# WifiTracker.net
KiCad netlist of a schematic drawn in EAGLE
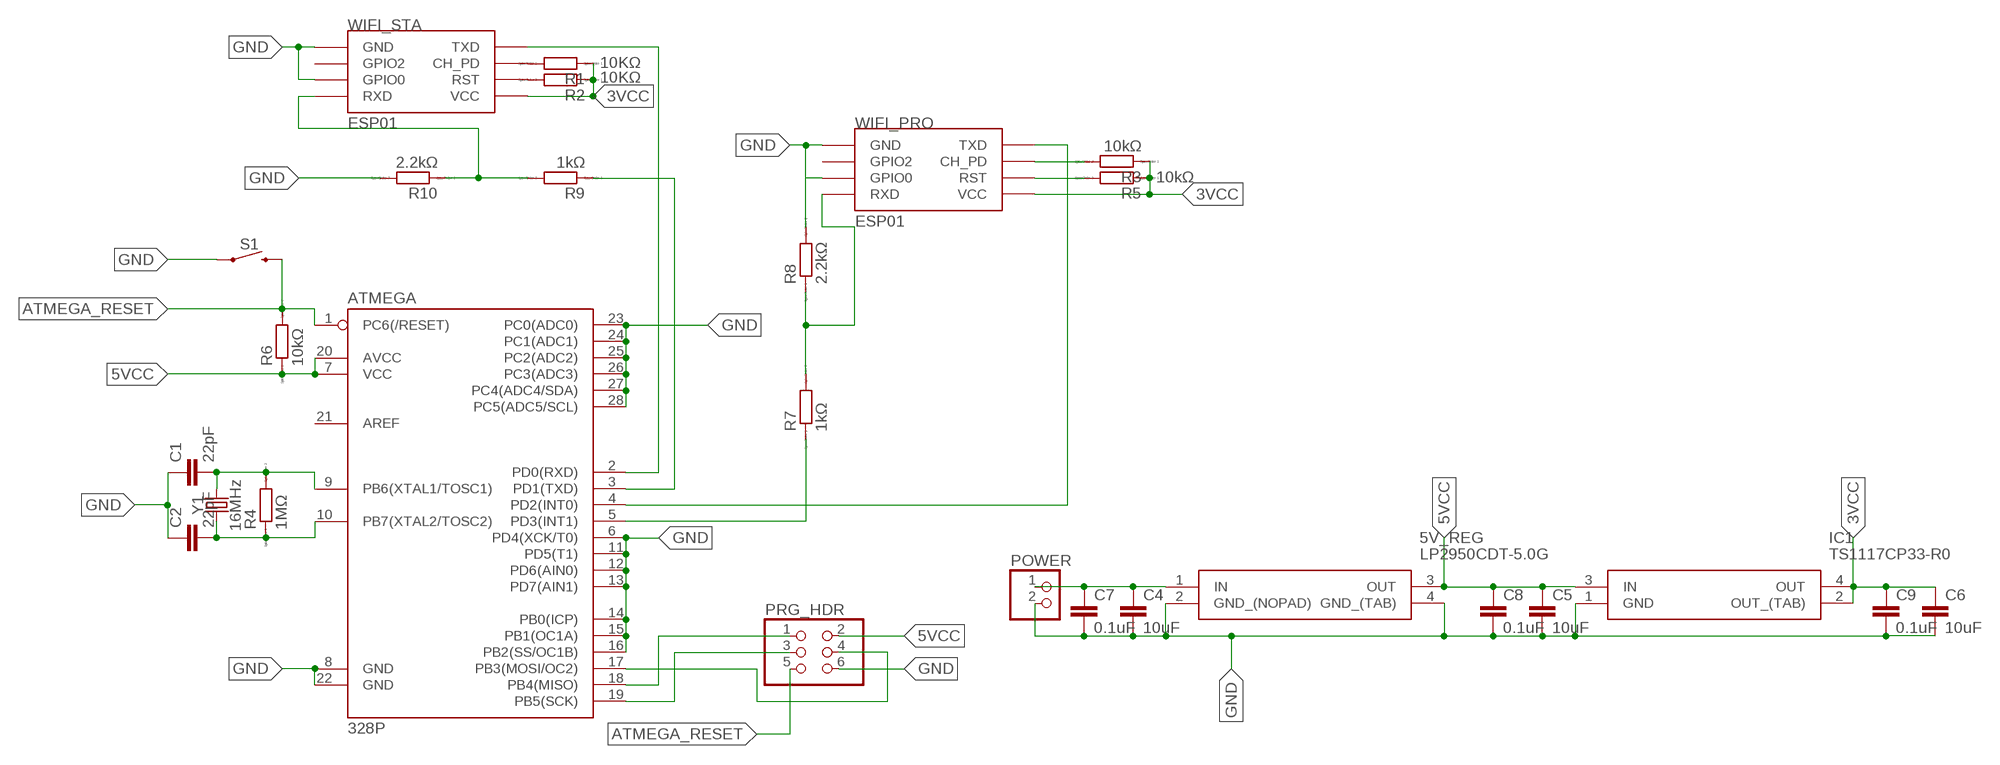
[diagram p0: schematic, sheet 1]

(export (version "E")
  (design (tool "Eeschema 10.0.6"))
  (components
    (comp (ref "5V_REG")
      (value "LP2950CDT-5.0G")
      (footprint "eagle-import:TO229P990X238-4N")
      (fields
        (field (name "MOUSER_PART_NUMBER") "863-LP2950CDT-5.0G")
        (field (name "RS_PART_NUMBER") "0463593P")
      )
      (libsource (lib "eagle-import") (part "LP2950CDT-5.0G"))
    )
    (comp (ref "ATMEGA")
      (value "328P")
      (footprint "eagle-import:DIP28")
      (libsource (lib "eagle-import") (part "ATMEGA328P_PDIP"))
    )
    (comp (ref "C1")
      (value "22pF")
      (footprint "eagle-import:1206")
      (libsource (lib "eagle-import") (part "1.0UF-1206-50V-10%"))
    )
    (comp (ref "C2")
      (value "22pF")
      (footprint "eagle-import:1206")
      (libsource (lib "eagle-import") (part "1.0UF-1206-50V-10%"))
    )
    (comp (ref "C4")
      (value "10uF")
      (footprint "eagle-import:1206")
      (libsource (lib "eagle-import") (part "1.0UF-1206-50V-10%"))
    )
    (comp (ref "C5")
      (value "10uF")
      (footprint "eagle-import:1206")
      (libsource (lib "eagle-import") (part "1.0UF-1206-50V-10%"))
    )
    (comp (ref "C6")
      (value "10uF")
      (footprint "eagle-import:1206")
      (libsource (lib "eagle-import") (part "1.0UF-1206-50V-10%"))
    )
    (comp (ref "C7")
      (value "0.1uF")
      (footprint "eagle-import:1206")
      (libsource (lib "eagle-import") (part "1.0UF-1206-50V-10%"))
    )
    (comp (ref "C8")
      (value "0.1uF")
      (footprint "eagle-import:1206")
      (libsource (lib "eagle-import") (part "1.0UF-1206-50V-10%"))
    )
    (comp (ref "C9")
      (value "0.1uF")
      (footprint "eagle-import:1206")
      (libsource (lib "eagle-import") (part "1.0UF-1206-50V-10%"))
    )
    (comp (ref "IC1")
      (value "TS1117CP33-R0")
      (footprint "eagle-import:TO229P990X238-4N")
      (fields
        (field (name "MANUFACTURER_PART_NUMBER") "LP2950CDT-5.0G")
        (field (name "MOUSER_PART_NUMBER") "863-LP2950CDT-5.0G")
        (field (name "RS_PART_NUMBER") "0463593P")
      )
      (libsource (lib "eagle-import") (part "TS1117CP33-R0"))
    )
    (comp (ref "POWER")
      (value "PINHD-1X2")
      (footprint "eagle-import:1X02")
      (libsource (lib "eagle-import") (part "PINHD-1X2"))
    )
    (comp (ref "PRG_HDR")
      (value "PINHD-2X3")
      (footprint "eagle-import:2X03")
      (libsource (lib "eagle-import") (part "PINHD-2X3"))
    )
    (comp (ref "R1")
      (value "10KΩ")
      (footprint "eagle-import:R1210")
      (libsource (lib "eagle-import") (part "RR1210"))
    )
    (comp (ref "R2")
      (value "10KΩ")
      (footprint "eagle-import:R1210")
      (libsource (lib "eagle-import") (part "RR1210"))
    )
    (comp (ref "R3")
      (value "10kΩ")
      (footprint "eagle-import:R1210")
      (libsource (lib "eagle-import") (part "RR1210"))
    )
    (comp (ref "R4")
      (value "1MΩ")
      (footprint "eagle-import:R1210")
      (libsource (lib "eagle-import") (part "RR1210"))
    )
    (comp (ref "R5")
      (value "10kΩ")
      (footprint "eagle-import:R1210")
      (libsource (lib "eagle-import") (part "RR1210"))
    )
    (comp (ref "R6")
      (value "10kΩ")
      (footprint "eagle-import:R1210")
      (libsource (lib "eagle-import") (part "RR1210"))
    )
    (comp (ref "R7")
      (value "1kΩ")
      (footprint "eagle-import:R1210")
      (libsource (lib "eagle-import") (part "RR1210"))
    )
    (comp (ref "R8")
      (value "2.2kΩ")
      (footprint "eagle-import:R1210")
      (libsource (lib "eagle-import") (part "RR1210"))
    )
    (comp (ref "R9")
      (value "1kΩ")
      (footprint "eagle-import:R1210")
      (libsource (lib "eagle-import") (part "RR1210"))
    )
    (comp (ref "R10")
      (value "2.2kΩ")
      (footprint "eagle-import:R1210")
      (libsource (lib "eagle-import") (part "RR1210"))
    )
    (comp (ref "S1")
      (value "MOMENTARY-SWITCH-SPST-PTH-6.0MM")
      (footprint "eagle-import:TACTILE_SWITCH_PTH_6.0MM")
      (libsource (lib "eagle-import") (part "MOMENTARY-SWITCH-SPST-PTH-6.0MM"))
    )
    (comp (ref "WIFI_PRO")
      (value "ESP01")
      (footprint "eagle-import:ESP01")
      (libsource (lib "eagle-import") (part "ESP01"))
    )
    (comp (ref "WIFI_STA")
      (value "ESP01")
      (footprint "eagle-import:ESP01")
      (libsource (lib "eagle-import") (part "ESP01"))
    )
    (comp (ref "Y1")
      (value "16MHz")
      (footprint "eagle-import:HC49UP")
      (libsource (lib "eagle-import") (part "CRYSTAL-8MHZSMD-HC49UP"))
    )
  )
  (nets
    (net (code "1") (name "3VCC") (class "Default")
      (node (ref "C6") (pin "1") (pinfunction "1_1") (pintype "passive"))
      (node (ref "C9") (pin "1") (pinfunction "1_1") (pintype "passive"))
      (node (ref "IC1") (pin "2") (pinfunction "OUT_(TAB)_2") (pintype "output"))
      (node (ref "IC1") (pin "4") (pinfunction "OUT_4") (pintype "output"))
      (node (ref "R1") (pin "1") (pinfunction "1_1") (pintype "passive"))
      (node (ref "R2") (pin "1") (pinfunction "1_1") (pintype "passive"))
      (node (ref "R3") (pin "1") (pinfunction "1_1") (pintype "passive"))
      (node (ref "R5") (pin "1") (pinfunction "1_1") (pintype "passive"))
      (node (ref "WIFI_PRO") (pin "VCC") (pinfunction "VCC_VCC") (pintype "bidirectional"))
      (node (ref "WIFI_STA") (pin "VCC") (pinfunction "VCC_VCC") (pintype "bidirectional"))
    )
    (net (code "2") (name "5VCC") (class "Default")
      (node (ref "5V_REG") (pin "3") (pinfunction "OUT_3") (pintype "output"))
      (node (ref "ATMEGA") (pin "20") (pinfunction "AVCC_20") (pintype "bidirectional"))
      (node (ref "ATMEGA") (pin "7") (pinfunction "VCC_7") (pintype "bidirectional"))
      (node (ref "C5") (pin "1") (pinfunction "1_1") (pintype "passive"))
      (node (ref "C8") (pin "1") (pinfunction "1_1") (pintype "passive"))
      (node (ref "IC1") (pin "3") (pinfunction "IN_3") (pintype "input"))
      (node (ref "PRG_HDR") (pin "2") (pinfunction "2_2") (pintype "passive"))
      (node (ref "R6") (pin "1") (pinfunction "1_1") (pintype "passive"))
    )
    (net (code "3") (name "ATMEGA_RESET") (class "Default")
      (node (ref "ATMEGA") (pin "1") (pinfunction "PC6(/RESET)_1") (pintype "bidirectional"))
      (node (ref "PRG_HDR") (pin "5") (pinfunction "5_5") (pintype "passive"))
      (node (ref "R6") (pin "2") (pinfunction "2_2") (pintype "passive"))
      (node (ref "S1") (pin "3") (pinfunction "2_3") (pintype "passive"))
    )
    (net (code "4") (name "GND") (class "Default")
      (node (ref "5V_REG") (pin "2") (pinfunction "GND_(NOPAD)_2") (pintype "power_in"))
      (node (ref "5V_REG") (pin "4") (pinfunction "GND_(TAB)_4") (pintype "power_in"))
      (node (ref "ATMEGA") (pin "11") (pinfunction "PD5(T1)_11") (pintype "bidirectional"))
      (node (ref "ATMEGA") (pin "12") (pinfunction "PD6(AIN0)_12") (pintype "bidirectional"))
      (node (ref "ATMEGA") (pin "13") (pinfunction "PD7(AIN1)_13") (pintype "bidirectional"))
      (node (ref "ATMEGA") (pin "14") (pinfunction "PB0(ICP)_14") (pintype "bidirectional"))
      (node (ref "ATMEGA") (pin "15") (pinfunction "PB1(OC1A)_15") (pintype "bidirectional"))
      (node (ref "ATMEGA") (pin "16") (pinfunction "PB2(SS/OC1B)_16") (pintype "bidirectional"))
      (node (ref "ATMEGA") (pin "22") (pinfunction "GND_22") (pintype "bidirectional"))
      (node (ref "ATMEGA") (pin "23") (pinfunction "PC0(ADC0)_23") (pintype "bidirectional"))
      (node (ref "ATMEGA") (pin "24") (pinfunction "PC1(ADC1)_24") (pintype "bidirectional"))
      (node (ref "ATMEGA") (pin "25") (pinfunction "PC2(ADC2)_25") (pintype "bidirectional"))
      (node (ref "ATMEGA") (pin "26") (pinfunction "PC3(ADC3)_26") (pintype "bidirectional"))
      (node (ref "ATMEGA") (pin "27") (pinfunction "PC4(ADC4/SDA)_27") (pintype "bidirectional"))
      (node (ref "ATMEGA") (pin "28") (pinfunction "PC5(ADC5/SCL)_28") (pintype "bidirectional"))
      (node (ref "ATMEGA") (pin "6") (pinfunction "PD4(XCK/T0)_6") (pintype "bidirectional"))
      (node (ref "ATMEGA") (pin "8") (pinfunction "GND_8") (pintype "bidirectional"))
      (node (ref "C1") (pin "1") (pinfunction "1_1") (pintype "passive"))
      (node (ref "C2") (pin "1") (pinfunction "1_1") (pintype "passive"))
      (node (ref "C4") (pin "2") (pinfunction "2_2") (pintype "passive"))
      (node (ref "C5") (pin "2") (pinfunction "2_2") (pintype "passive"))
      (node (ref "C6") (pin "2") (pinfunction "2_2") (pintype "passive"))
      (node (ref "C7") (pin "2") (pinfunction "2_2") (pintype "passive"))
      (node (ref "C8") (pin "2") (pinfunction "2_2") (pintype "passive"))
      (node (ref "C9") (pin "2") (pinfunction "2_2") (pintype "passive"))
      (node (ref "IC1") (pin "1") (pinfunction "GND_1") (pintype "power_in"))
      (node (ref "POWER") (pin "2") (pinfunction "2_2") (pintype "passive"))
      (node (ref "PRG_HDR") (pin "6") (pinfunction "6_6") (pintype "passive"))
      (node (ref "R10") (pin "2") (pinfunction "2_2") (pintype "passive"))
      (node (ref "R8") (pin "2") (pinfunction "2_2") (pintype "passive"))
      (node (ref "S1") (pin "1") (pinfunction "1_1") (pintype "passive"))
      (node (ref "WIFI_PRO") (pin "GND") (pinfunction "GND_GND") (pintype "bidirectional"))
      (node (ref "WIFI_PRO") (pin "GPIO0") (pinfunction "GPIO0_GPIO0") (pintype "bidirectional"))
      (node (ref "WIFI_STA") (pin "GND") (pinfunction "GND_GND") (pintype "bidirectional"))
      (node (ref "WIFI_STA") (pin "GPIO0") (pinfunction "GPIO0_GPIO0") (pintype "bidirectional"))
    )
    (net (code "5") (name "Net-(5V_REG-IN)") (class "Default")
      (node (ref "5V_REG") (pin "1") (pinfunction "IN_1") (pintype "input"))
      (node (ref "C4") (pin "1") (pinfunction "1_1") (pintype "passive"))
      (node (ref "C7") (pin "1") (pinfunction "1_1") (pintype "passive"))
      (node (ref "POWER") (pin "1") (pinfunction "1_1") (pintype "passive"))
    )
    (net (code "6") (name "Net-(ATMEGA-PB3(MOSI{slash}OC2))") (class "Default")
      (node (ref "ATMEGA") (pin "17") (pinfunction "PB3(MOSI/OC2)_17") (pintype "bidirectional"))
      (node (ref "PRG_HDR") (pin "4") (pinfunction "4_4") (pintype "passive"))
    )
    (net (code "7") (name "Net-(ATMEGA-PB4(MISO))") (class "Default")
      (node (ref "ATMEGA") (pin "18") (pinfunction "PB4(MISO)_18") (pintype "bidirectional"))
      (node (ref "PRG_HDR") (pin "1") (pinfunction "1_1") (pintype "passive"))
    )
    (net (code "8") (name "Net-(ATMEGA-PB5(SCK))") (class "Default")
      (node (ref "ATMEGA") (pin "19") (pinfunction "PB5(SCK)_19") (pintype "bidirectional"))
      (node (ref "PRG_HDR") (pin "3") (pinfunction "3_3") (pintype "passive"))
    )
    (net (code "9") (name "Net-(ATMEGA-PB6(XTAL1{slash}TOSC1))") (class "Default")
      (node (ref "ATMEGA") (pin "9") (pinfunction "PB6(XTAL1/TOSC1)_9") (pintype "bidirectional"))
      (node (ref "C1") (pin "2") (pinfunction "2_2") (pintype "passive"))
      (node (ref "R4") (pin "2") (pinfunction "2_2") (pintype "passive"))
      (node (ref "Y1") (pin "2") (pinfunction "2_2") (pintype "passive"))
    )
    (net (code "10") (name "Net-(ATMEGA-PB7(XTAL2{slash}TOSC2))") (class "Default")
      (node (ref "ATMEGA") (pin "10") (pinfunction "PB7(XTAL2/TOSC2)_10") (pintype "bidirectional"))
      (node (ref "C2") (pin "2") (pinfunction "2_2") (pintype "passive"))
      (node (ref "R4") (pin "1") (pinfunction "1_1") (pintype "passive"))
      (node (ref "Y1") (pin "1") (pinfunction "1_1") (pintype "passive"))
    )
    (net (code "11") (name "Net-(ATMEGA-PD0(RXD))") (class "Default")
      (node (ref "ATMEGA") (pin "2") (pinfunction "PD0(RXD)_2") (pintype "bidirectional"))
      (node (ref "WIFI_STA") (pin "TX") (pinfunction "TXD_TX") (pintype "bidirectional"))
    )
    (net (code "12") (name "Net-(ATMEGA-PD1(TXD))") (class "Default")
      (node (ref "ATMEGA") (pin "3") (pinfunction "PD1(TXD)_3") (pintype "bidirectional"))
      (node (ref "R9") (pin "1") (pinfunction "1_1") (pintype "passive"))
    )
    (net (code "13") (name "Net-(ATMEGA-PD2(INT0))") (class "Default")
      (node (ref "ATMEGA") (pin "4") (pinfunction "PD2(INT0)_4") (pintype "bidirectional"))
      (node (ref "WIFI_PRO") (pin "TX") (pinfunction "TXD_TX") (pintype "bidirectional"))
    )
    (net (code "14") (name "Net-(ATMEGA-PD3(INT1))") (class "Default")
      (node (ref "ATMEGA") (pin "5") (pinfunction "PD3(INT1)_5") (pintype "bidirectional"))
      (node (ref "R7") (pin "1") (pinfunction "1_1") (pintype "passive"))
    )
    (net (code "15") (name "Net-(R1-Pad2)") (class "Default")
      (node (ref "R1") (pin "2") (pinfunction "2_2") (pintype "passive"))
      (node (ref "WIFI_STA") (pin "CH_PD") (pinfunction "CH_PD_CH_PD") (pintype "bidirectional"))
    )
    (net (code "16") (name "Net-(R2-Pad2)") (class "Default")
      (node (ref "R2") (pin "2") (pinfunction "2_2") (pintype "passive"))
      (node (ref "WIFI_STA") (pin "RST") (pinfunction "RST_RST") (pintype "bidirectional"))
    )
    (net (code "17") (name "Net-(R3-Pad2)") (class "Default")
      (node (ref "R3") (pin "2") (pinfunction "2_2") (pintype "passive"))
      (node (ref "WIFI_PRO") (pin "CH_PD") (pinfunction "CH_PD_CH_PD") (pintype "bidirectional"))
    )
    (net (code "18") (name "Net-(R5-Pad2)") (class "Default")
      (node (ref "R5") (pin "2") (pinfunction "2_2") (pintype "passive"))
      (node (ref "WIFI_PRO") (pin "RST") (pinfunction "RST_RST") (pintype "bidirectional"))
    )
    (net (code "19") (name "Net-(WIFI_PRO-RXD)") (class "Default")
      (node (ref "R7") (pin "2") (pinfunction "2_2") (pintype "passive"))
      (node (ref "R8") (pin "1") (pinfunction "1_1") (pintype "passive"))
      (node (ref "WIFI_PRO") (pin "RX") (pinfunction "RXD_RX") (pintype "bidirectional"))
    )
    (net (code "20") (name "Net-(WIFI_STA-RXD)") (class "Default")
      (node (ref "R10") (pin "1") (pinfunction "1_1") (pintype "passive"))
      (node (ref "R9") (pin "2") (pinfunction "2_2") (pintype "passive"))
      (node (ref "WIFI_STA") (pin "RX") (pinfunction "RXD_RX") (pintype "bidirectional"))
    )
    (net (code "21") (name "unconnected-(ATMEGA-AREF-Pad21)") (class "Default")
      (node (ref "ATMEGA") (pin "21") (pinfunction "AREF_21") (pintype "bidirectional"))
    )
    (net (code "22") (name "unconnected-(WIFI_PRO-PadGPIO2)") (class "Default")
      (node (ref "WIFI_PRO") (pin "GPIO2") (pinfunction "GPIO2_GPIO2") (pintype "bidirectional"))
    )
    (net (code "23") (name "unconnected-(WIFI_STA-PadGPIO2)") (class "Default")
      (node (ref "WIFI_STA") (pin "GPIO2") (pinfunction "GPIO2_GPIO2") (pintype "bidirectional"))
    )
  )
)
